# keypad.net
KiCad netlist of a schematic drawn in EAGLE
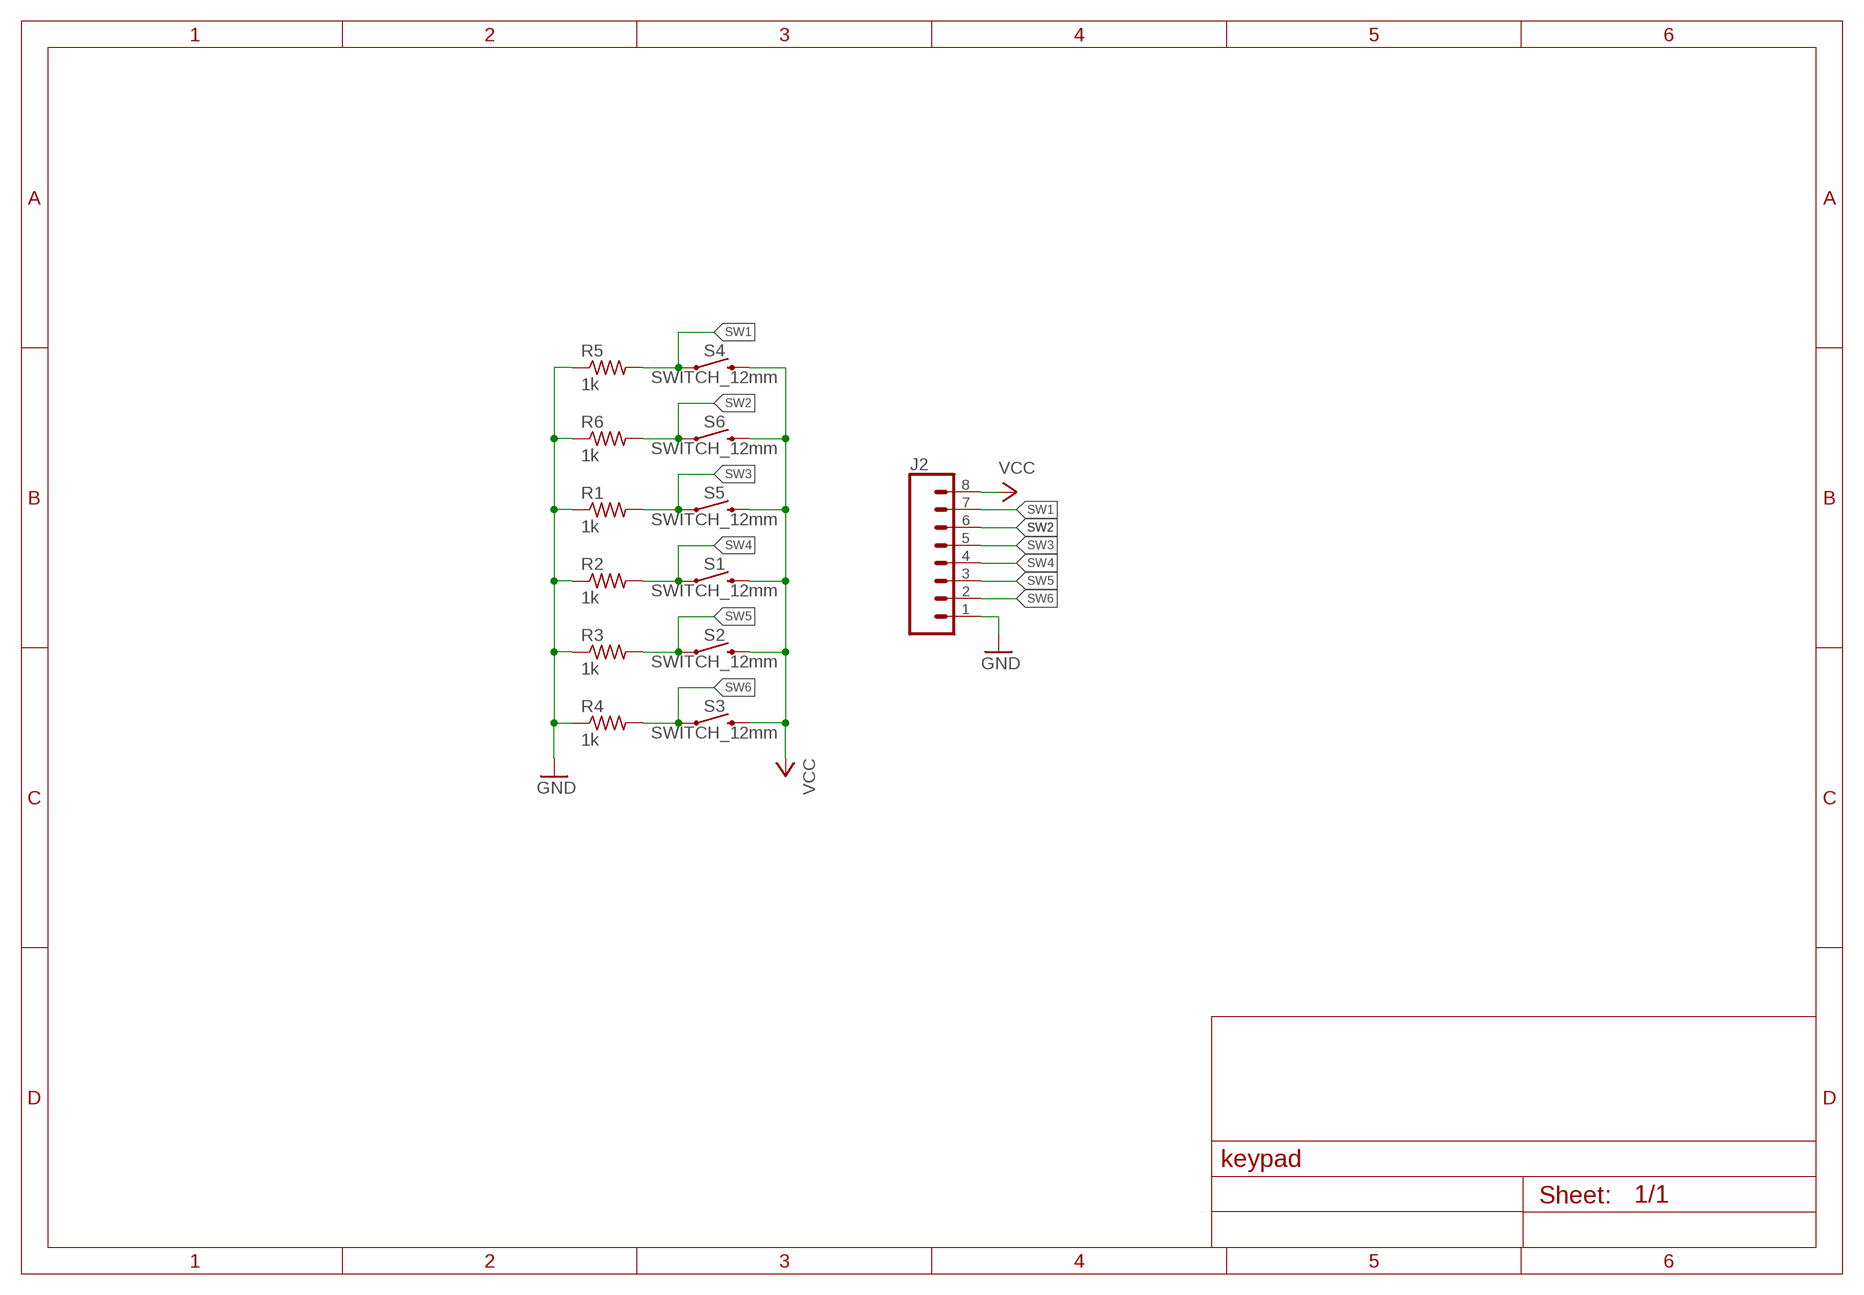
[diagram p0: schematic, sheet 1]

(export (version "E")
  (design (tool "Eeschema 10.0.6"))
  (components
    (comp (ref "J2")
      (value "CONN_08LONGPADS")
      (footprint "eagle-import:1X08_LONGPADS")
      (libsource (lib "eagle-import") (part "CONN_08LONGPADS"))
    )
    (comp (ref "R1")
      (value "1k")
      (footprint "eagle-import:0207_10")
      (libsource (lib "eagle-import") (part "R-US_0207/10"))
    )
    (comp (ref "R2")
      (value "1k")
      (footprint "eagle-import:0207_10")
      (libsource (lib "eagle-import") (part "R-US_0207/10"))
    )
    (comp (ref "R3")
      (value "1k")
      (footprint "eagle-import:0207_10")
      (libsource (lib "eagle-import") (part "R-US_0207/10"))
    )
    (comp (ref "R4")
      (value "1k")
      (footprint "eagle-import:0207_10")
      (libsource (lib "eagle-import") (part "R-US_0207/10"))
    )
    (comp (ref "R5")
      (value "1k")
      (footprint "eagle-import:0207_10")
      (libsource (lib "eagle-import") (part "R-US_0207/10"))
    )
    (comp (ref "R6")
      (value "1k")
      (footprint "eagle-import:0207_10")
      (libsource (lib "eagle-import") (part "R-US_0207/10"))
    )
    (comp (ref "S1")
      (value "SWITCH_12mm")
      (footprint "eagle-import:TACTILE_SWITCH_PTH_12MM")
      (libsource (lib "eagle-import") (part "MOMENTARY-SWITCH-SPST-PTH-12MM"))
    )
    (comp (ref "S2")
      (value "SWITCH_12mm")
      (footprint "eagle-import:TACTILE_SWITCH_PTH_12MM")
      (libsource (lib "eagle-import") (part "MOMENTARY-SWITCH-SPST-PTH-12MM"))
    )
    (comp (ref "S3")
      (value "SWITCH_12mm")
      (footprint "eagle-import:TACTILE_SWITCH_PTH_12MM")
      (libsource (lib "eagle-import") (part "MOMENTARY-SWITCH-SPST-PTH-12MM"))
    )
    (comp (ref "S4")
      (value "SWITCH_12mm")
      (footprint "eagle-import:TACTILE_SWITCH_PTH_12MM")
      (libsource (lib "eagle-import") (part "MOMENTARY-SWITCH-SPST-PTH-12MM"))
    )
    (comp (ref "S5")
      (value "SWITCH_12mm")
      (footprint "eagle-import:TACTILE_SWITCH_PTH_12MM")
      (libsource (lib "eagle-import") (part "MOMENTARY-SWITCH-SPST-PTH-12MM"))
    )
    (comp (ref "S6")
      (value "SWITCH_12mm")
      (footprint "eagle-import:TACTILE_SWITCH_PTH_12MM")
      (libsource (lib "eagle-import") (part "MOMENTARY-SWITCH-SPST-PTH-12MM"))
    )
  )
  (nets
    (net (code "1") (name "GND") (class "Default")
      (node (ref "J2") (pin "1") (pinfunction "1_1") (pintype "passive"))
      (node (ref "R1") (pin "1") (pinfunction "1_1") (pintype "passive"))
      (node (ref "R2") (pin "1") (pinfunction "1_1") (pintype "passive"))
      (node (ref "R3") (pin "1") (pinfunction "1_1") (pintype "passive"))
      (node (ref "R4") (pin "1") (pinfunction "1_1") (pintype "passive"))
      (node (ref "R5") (pin "1") (pinfunction "1_1") (pintype "passive"))
      (node (ref "R6") (pin "1") (pinfunction "1_1") (pintype "passive"))
    )
    (net (code "2") (name "SW1") (class "Default")
      (node (ref "J2") (pin "7") (pinfunction "7_7") (pintype "passive"))
      (node (ref "R5") (pin "2") (pinfunction "2_2") (pintype "passive"))
      (node (ref "S4") (pin "1") (pinfunction "1_1") (pintype "passive"))
    )
    (net (code "3") (name "SW2") (class "Default")
      (node (ref "J2") (pin "6") (pinfunction "6_6") (pintype "passive"))
      (node (ref "R6") (pin "2") (pinfunction "2_2") (pintype "passive"))
      (node (ref "S6") (pin "1") (pinfunction "1_1") (pintype "passive"))
    )
    (net (code "4") (name "SW3") (class "Default")
      (node (ref "J2") (pin "5") (pinfunction "5_5") (pintype "passive"))
      (node (ref "R1") (pin "2") (pinfunction "2_2") (pintype "passive"))
      (node (ref "S5") (pin "1") (pinfunction "1_1") (pintype "passive"))
    )
    (net (code "5") (name "SW4") (class "Default")
      (node (ref "J2") (pin "4") (pinfunction "4_4") (pintype "passive"))
      (node (ref "R2") (pin "2") (pinfunction "2_2") (pintype "passive"))
      (node (ref "S1") (pin "1") (pinfunction "1_1") (pintype "passive"))
    )
    (net (code "6") (name "SW5") (class "Default")
      (node (ref "J2") (pin "3") (pinfunction "3_3") (pintype "passive"))
      (node (ref "R3") (pin "2") (pinfunction "2_2") (pintype "passive"))
      (node (ref "S2") (pin "1") (pinfunction "1_1") (pintype "passive"))
    )
    (net (code "7") (name "SW6") (class "Default")
      (node (ref "J2") (pin "2") (pinfunction "2_2") (pintype "passive"))
      (node (ref "R4") (pin "2") (pinfunction "2_2") (pintype "passive"))
      (node (ref "S3") (pin "1") (pinfunction "1_1") (pintype "passive"))
    )
    (net (code "8") (name "VCC") (class "Default")
      (node (ref "J2") (pin "8") (pinfunction "8_8") (pintype "passive"))
      (node (ref "S1") (pin "3") (pinfunction "2_3") (pintype "passive"))
      (node (ref "S2") (pin "3") (pinfunction "2_3") (pintype "passive"))
      (node (ref "S3") (pin "3") (pinfunction "2_3") (pintype "passive"))
      (node (ref "S4") (pin "3") (pinfunction "2_3") (pintype "passive"))
      (node (ref "S5") (pin "3") (pinfunction "2_3") (pintype "passive"))
      (node (ref "S6") (pin "3") (pinfunction "2_3") (pintype "passive"))
    )
  )
)
